# P05_CPLD.net
KiCad netlist of a schematic drawn in Altium Designer
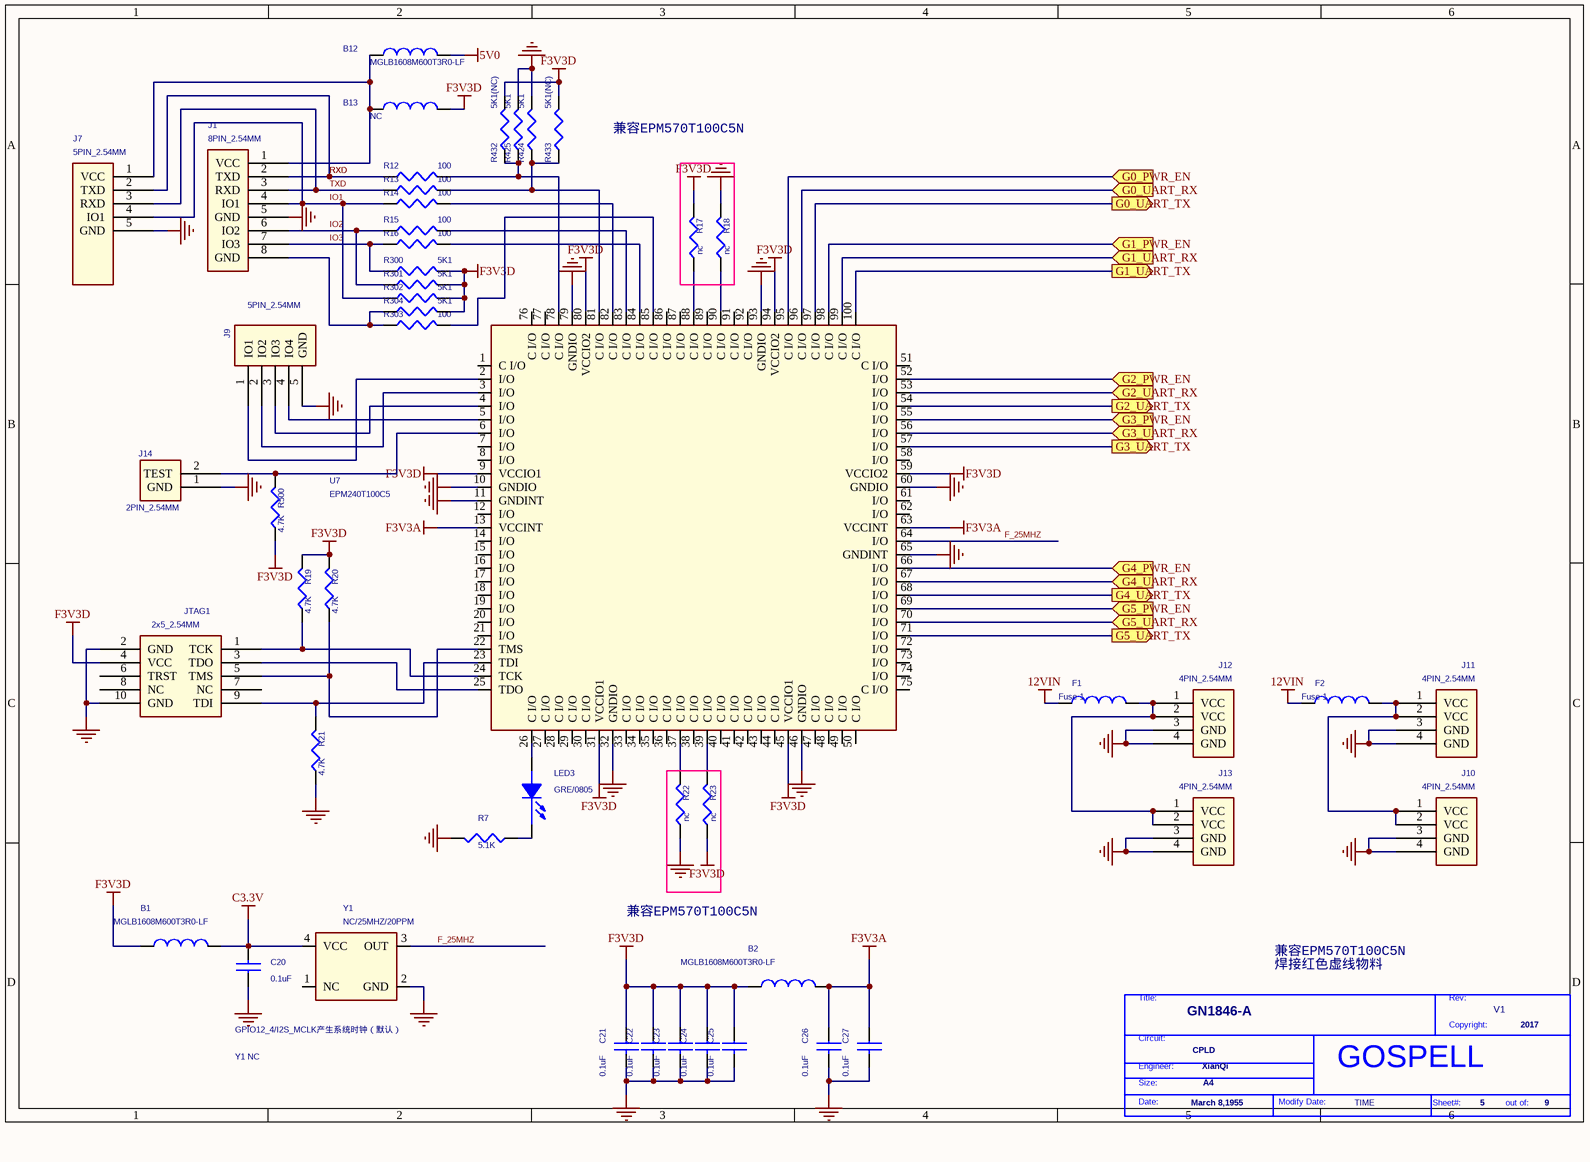
[diagram p0: P05 CPLD.SchDoc]

(export (version "E")
  (design (tool "Eeschema 10.0.6"))
  (components
    (comp (ref "B1") (value "MGLB1608M600T3R0-LF") (libsource (lib "*") (part "CHOKE TORROID_0")))
    (comp (ref "B2") (value "MGLB1608M600T3R0-LF") (libsource (lib "*") (part "CHOKE TORROID_0")))
    (comp (ref "B12") (value "MGLB1608M600T3R0-LF") (libsource (lib "*") (part "CHOKE TORROID_0")))
    (comp (ref "B13") (value "NC") (libsource (lib "*") (part "CHOKE TORROID_0")))
    (comp (ref "C20") (value "0.1uF") (libsource (lib "*") (part "CAP NP")))
    (comp (ref "C21") (value "0.1uF") (libsource (lib "*") (part "CAP NP_Dup1")))
    (comp (ref "C22") (value "0.1uF") (libsource (lib "*") (part "CAP NP_Dup1")))
    (comp (ref "C23") (value "0.1uF") (libsource (lib "*") (part "CAP NP_Dup1")))
    (comp (ref "C24") (value "0.1uF") (libsource (lib "*") (part "CAP NP_Dup1")))
    (comp (ref "C25") (value "0.1uF") (libsource (lib "*") (part "CAP NP_Dup1")))
    (comp (ref "C26") (value "0.1uF") (libsource (lib "*") (part "CAP NP_Dup1")))
    (comp (ref "C27") (value "0.1uF") (libsource (lib "*") (part "CAP NP_Dup1")))
    (comp (ref "F1") (value "Fuse 1") (libsource (lib "*") (part "CHOKE TORROID_0")))
    (comp (ref "F2") (value "Fuse 1") (libsource (lib "*") (part "CHOKE TORROID_0")))
    (comp (ref "J1") (value "8PIN_2.54MM") (libsource (lib "*") (part "CON8_0")))
    (comp (ref "J7") (value "5PIN_2.54MM") (libsource (lib "*") (part "CON8_1")))
    (comp (ref "J9") (value "5PIN_2.54MM") (libsource (lib "") (part "CON8_1_1")))
    (comp (ref "J10") (value "4PIN_2.54MM") (libsource (lib "GN-1846-A-V1") (part "CON8_1")))
    (comp (ref "J11") (value "4PIN_2.54MM") (libsource (lib "GN-1846-A-V1") (part "CON8_1")))
    (comp (ref "J12") (value "4PIN_2.54MM") (libsource (lib "GN-1846-A-V1") (part "CON8_1")))
    (comp (ref "J13") (value "4PIN_2.54MM") (libsource (lib "GN-1846-A-V1") (part "CON8_1")))
    (comp (ref "J14") (value "2PIN_2.54MM") (libsource (lib "GN-1846-A-V2") (part "CON8_1")))
    (comp (ref "JTAG1") (value "2x5_2.54MM") (libsource (lib "*") (part "CON10A_0")))
    (comp (ref "LED3") (value "GRE/0805") (libsource (lib "*") (part "LED_0")))
    (comp (ref "R7") (value "5.1K") (libsource (lib "") (part "R_Dup1_1")))
    (comp (ref "R12") (value "100") (libsource (lib "*") (part "R_Dup1")))
    (comp (ref "R13") (value "100") (libsource (lib "*") (part "R_Dup1")))
    (comp (ref "R14") (value "100") (libsource (lib "*") (part "R_Dup1")))
    (comp (ref "R15") (value "100") (libsource (lib "*") (part "R_Dup1")))
    (comp (ref "R16") (value "100") (libsource (lib "*") (part "R_Dup1")))
    (comp (ref "R17") (value "nc") (libsource (lib "*") (part "R_Dup1")))
    (comp (ref "R18") (value "nc") (libsource (lib "*") (part "R_Dup1")))
    (comp (ref "R19") (value "4.7K") (libsource (lib "*") (part "R_Dup1")))
    (comp (ref "R20") (value "4.7K") (libsource (lib "*") (part "R_Dup1")))
    (comp (ref "R21") (value "4.7K") (libsource (lib "*") (part "R_Dup1")))
    (comp (ref "R22") (value "nc") (libsource (lib "*") (part "R_Dup1")))
    (comp (ref "R23") (value "nc") (libsource (lib "*") (part "R_Dup1")))
    (comp (ref "R300") (value "5K1") (libsource (lib "*") (part "R_Dup1")))
    (comp (ref "R301") (value "5K1") (libsource (lib "*") (part "R_Dup1")))
    (comp (ref "R302") (value "5K1") (libsource (lib "*") (part "R_Dup1")))
    (comp (ref "R303") (value "100") (libsource (lib "*") (part "R_Dup1")))
    (comp (ref "R304") (value "5K1") (libsource (lib "*") (part "R_Dup1")))
    (comp (ref "R424") (value "5K1") (libsource (lib "") (part "R_Dup1_1")))
    (comp (ref "R425") (value "5K1") (libsource (lib "") (part "R_Dup1_1")))
    (comp (ref "R432") (value "5K1(NC)") (libsource (lib "") (part "R_Dup1_1")))
    (comp (ref "R433") (value "5K1(NC)") (libsource (lib "") (part "R_Dup1_1")))
    (comp (ref "R500") (value "4.7K") (libsource (lib "*") (part "R_Dup1")))
    (comp (ref "U7") (value "EPM240T100C5") (libsource (lib "*") (part "EPM240T100C5")))
    (comp (ref "Y1") (value "NC/25MHZ/20PPM") (footprint "SCXO_7.0X5.0") (libsource (lib "*") (part "SCXO")))
  )
  (nets
    (net (code "1") (name "/F_25MHZ") (class "Default")
      (node (ref "U7") (pin "64") (pinfunction "I/O_64") (pintype "passive"))
      (node (ref "Y1") (pin "3") (pinfunction "OUT_3") (pintype "passive"))
    )
    (net (code "2") (name "/G0_PWR_EN") (class "Default")
      (node (ref "U7") (pin "95") (pinfunction "C_I/O_95") (pintype "passive"))
    )
    (net (code "3") (name "/G0_UART_RX") (class "Default")
      (node (ref "U7") (pin "96") (pinfunction "C_I/O_96") (pintype "passive"))
    )
    (net (code "4") (name "/G0_UART_TX") (class "Default")
      (node (ref "U7") (pin "97") (pinfunction "C_I/O_97") (pintype "passive"))
    )
    (net (code "5") (name "/G1_PWR_EN") (class "Default")
      (node (ref "U7") (pin "98") (pinfunction "C_I/O_98") (pintype "passive"))
    )
    (net (code "6") (name "/G1_UART_RX") (class "Default")
      (node (ref "U7") (pin "99") (pinfunction "C_I/O_99") (pintype "passive"))
    )
    (net (code "7") (name "/G1_UART_TX") (class "Default")
      (node (ref "U7") (pin "100") (pinfunction "C_I/O_100") (pintype "passive"))
    )
    (net (code "8") (name "/G2_PWR_EN") (class "Default")
      (node (ref "U7") (pin "52") (pinfunction "I/O_52") (pintype "passive"))
    )
    (net (code "9") (name "/G2_UART_RX") (class "Default")
      (node (ref "U7") (pin "53") (pinfunction "I/O_53") (pintype "passive"))
    )
    (net (code "10") (name "/G2_UART_TX") (class "Default")
      (node (ref "U7") (pin "54") (pinfunction "I/O_54") (pintype "passive"))
    )
    (net (code "11") (name "/G3_PWR_EN") (class "Default")
      (node (ref "U7") (pin "55") (pinfunction "I/O_55") (pintype "passive"))
    )
    (net (code "12") (name "/G3_UART_RX") (class "Default")
      (node (ref "U7") (pin "56") (pinfunction "I/O_56") (pintype "passive"))
    )
    (net (code "13") (name "/G3_UART_TX") (class "Default")
      (node (ref "U7") (pin "57") (pinfunction "I/O_57") (pintype "passive"))
    )
    (net (code "14") (name "/G4_PWR_EN") (class "Default")
      (node (ref "U7") (pin "66") (pinfunction "I/O_66") (pintype "passive"))
    )
    (net (code "15") (name "/G4_UART_RX") (class "Default")
      (node (ref "U7") (pin "67") (pinfunction "I/O_67") (pintype "passive"))
    )
    (net (code "16") (name "/G4_UART_TX") (class "Default")
      (node (ref "U7") (pin "68") (pinfunction "I/O_68") (pintype "passive"))
    )
    (net (code "17") (name "/G5_PWR_EN") (class "Default")
      (node (ref "U7") (pin "69") (pinfunction "I/O_69") (pintype "passive"))
    )
    (net (code "18") (name "/G5_UART_RX") (class "Default")
      (node (ref "U7") (pin "70") (pinfunction "I/O_70") (pintype "passive"))
    )
    (net (code "19") (name "/G5_UART_TX") (class "Default")
      (node (ref "U7") (pin "71") (pinfunction "I/O_71") (pintype "passive"))
    )
    (net (code "20") (name "/IO1") (class "Default")
      (node (ref "J1") (pin "4") (pinfunction "IO1_4") (pintype "passive"))
      (node (ref "J7") (pin "4") (pinfunction "IO1_4") (pintype "passive"))
      (node (ref "R14") (pin "2") (pinfunction "2_2") (pintype "passive"))
      (node (ref "R302") (pin "2") (pinfunction "2_2") (pintype "passive"))
    )
    (net (code "21") (name "/IO2") (class "Default")
      (node (ref "J1") (pin "6") (pinfunction "IO2_6") (pintype "passive"))
      (node (ref "R15") (pin "2") (pinfunction "2_2") (pintype "passive"))
      (node (ref "R301") (pin "2") (pinfunction "2_2") (pintype "passive"))
    )
    (net (code "22") (name "/IO3") (class "Default")
      (node (ref "J1") (pin "7") (pinfunction "IO3_7") (pintype "passive"))
      (node (ref "R16") (pin "2") (pinfunction "2_2") (pintype "passive"))
      (node (ref "R300") (pin "2") (pinfunction "2_2") (pintype "passive"))
    )
    (net (code "23") (name "/RXD") (class "Default")
      (node (ref "J1") (pin "2") (pinfunction "TXD_2") (pintype "passive"))
      (node (ref "J7") (pin "2") (pinfunction "TXD_2") (pintype "passive"))
      (node (ref "R12") (pin "2") (pinfunction "2_2") (pintype "passive"))
    )
    (net (code "24") (name "/TXD") (class "Default")
      (node (ref "J1") (pin "3") (pinfunction "RXD_3") (pintype "passive"))
      (node (ref "J7") (pin "3") (pinfunction "RXD_3") (pintype "passive"))
      (node (ref "R13") (pin "2") (pinfunction "2_2") (pintype "passive"))
    )
    (net (code "25") (name "5V0") (class "Default")
      (node (ref "B12") (pin "2") (pinfunction "2_2") (pintype "passive"))
    )
    (net (code "26") (name "12VIN") (class "Default")
      (node (ref "F1") (pin "1") (pinfunction "1_1") (pintype "passive"))
      (node (ref "F2") (pin "1") (pinfunction "1_1") (pintype "passive"))
    )
    (net (code "27") (name "C3.3V") (class "Default")
      (node (ref "B1") (pin "2") (pinfunction "2_2") (pintype "passive"))
      (node (ref "C20") (pin "2") (pinfunction "2_2") (pintype "passive"))
      (node (ref "Y1") (pin "4") (pinfunction "VCC_4") (pintype "passive"))
    )
    (net (code "28") (name "F3V3A") (class "Default")
      (node (ref "B2") (pin "2") (pinfunction "2_2") (pintype "passive"))
      (node (ref "C26") (pin "1") (pinfunction "1_1") (pintype "passive"))
      (node (ref "C27") (pin "1") (pinfunction "1_1") (pintype "passive"))
      (node (ref "U7") (pin "13") (pinfunction "VCCINT_13") (pintype "passive"))
      (node (ref "U7") (pin "63") (pinfunction "VCCINT_63") (pintype "passive"))
    )
    (net (code "29") (name "F3V3D") (class "Default")
      (node (ref "B1") (pin "1") (pinfunction "1_1") (pintype "passive"))
      (node (ref "B13") (pin "2") (pinfunction "2_2") (pintype "passive"))
      (node (ref "B2") (pin "1") (pinfunction "1_1") (pintype "passive"))
      (node (ref "C21") (pin "1") (pinfunction "1_1") (pintype "passive"))
      (node (ref "C22") (pin "1") (pinfunction "1_1") (pintype "passive"))
      (node (ref "C23") (pin "1") (pinfunction "1_1") (pintype "passive"))
      (node (ref "C24") (pin "1") (pinfunction "1_1") (pintype "passive"))
      (node (ref "C25") (pin "1") (pinfunction "1_1") (pintype "passive"))
      (node (ref "JTAG1") (pin "4") (pinfunction "VCC_4") (pintype "passive"))
      (node (ref "R17") (pin "1") (pinfunction "1_1") (pintype "passive"))
      (node (ref "R19") (pin "1") (pinfunction "1_1") (pintype "passive"))
      (node (ref "R20") (pin "1") (pinfunction "1_1") (pintype "passive"))
      (node (ref "R23") (pin "2") (pinfunction "2_2") (pintype "passive"))
      (node (ref "R300") (pin "1") (pinfunction "1_1") (pintype "passive"))
      (node (ref "R301") (pin "1") (pinfunction "1_1") (pintype "passive"))
      (node (ref "R302") (pin "1") (pinfunction "1_1") (pintype "passive"))
      (node (ref "R304") (pin "1") (pinfunction "1_1") (pintype "passive"))
      (node (ref "R432") (pin "1") (pinfunction "1_1") (pintype "passive"))
      (node (ref "R433") (pin "1") (pinfunction "1_1") (pintype "passive"))
      (node (ref "R500") (pin "2") (pinfunction "2_2") (pintype "passive"))
      (node (ref "U7") (pin "31") (pinfunction "VCCIO1_31") (pintype "passive"))
      (node (ref "U7") (pin "45") (pinfunction "VCCIO1_45") (pintype "passive"))
      (node (ref "U7") (pin "59") (pinfunction "VCCIO2_59") (pintype "passive"))
      (node (ref "U7") (pin "80") (pinfunction "VCCIO2_80") (pintype "passive"))
      (node (ref "U7") (pin "9") (pinfunction "VCCIO1_9") (pintype "passive"))
      (node (ref "U7") (pin "94") (pinfunction "VCCIO2_94") (pintype "passive"))
    )
    (net (code "30") (name "GND") (class "Default")
      (node (ref "C20") (pin "1") (pinfunction "1_1") (pintype "passive"))
      (node (ref "C21") (pin "2") (pinfunction "2_2") (pintype "passive"))
      (node (ref "C22") (pin "2") (pinfunction "2_2") (pintype "passive"))
      (node (ref "C23") (pin "2") (pinfunction "2_2") (pintype "passive"))
      (node (ref "C24") (pin "2") (pinfunction "2_2") (pintype "passive"))
      (node (ref "C25") (pin "2") (pinfunction "2_2") (pintype "passive"))
      (node (ref "C26") (pin "2") (pinfunction "2_2") (pintype "passive"))
      (node (ref "C27") (pin "2") (pinfunction "2_2") (pintype "passive"))
      (node (ref "J1") (pin "5") (pinfunction "GND_5") (pintype "passive"))
      (node (ref "J10") (pin "3") (pinfunction "GND_3") (pintype "passive"))
      (node (ref "J10") (pin "4") (pinfunction "GND_4") (pintype "passive"))
      (node (ref "J11") (pin "3") (pinfunction "GND_3") (pintype "passive"))
      (node (ref "J11") (pin "4") (pinfunction "GND_4") (pintype "passive"))
      (node (ref "J12") (pin "3") (pinfunction "GND_3") (pintype "passive"))
      (node (ref "J12") (pin "4") (pinfunction "GND_4") (pintype "passive"))
      (node (ref "J13") (pin "3") (pinfunction "GND_3") (pintype "passive"))
      (node (ref "J13") (pin "4") (pinfunction "GND_4") (pintype "passive"))
      (node (ref "J14") (pin "1") (pinfunction "GND_1") (pintype "passive"))
      (node (ref "J7") (pin "5") (pinfunction "GND_5") (pintype "passive"))
      (node (ref "J9") (pin "5") (pinfunction "GND_5") (pintype "passive"))
      (node (ref "JTAG1") (pin "10") (pinfunction "GND_10") (pintype "passive"))
      (node (ref "JTAG1") (pin "2") (pinfunction "GND_2") (pintype "passive"))
      (node (ref "R18") (pin "1") (pinfunction "1_1") (pintype "passive"))
      (node (ref "R21") (pin "2") (pinfunction "2_2") (pintype "passive"))
      (node (ref "R22") (pin "2") (pinfunction "2_2") (pintype "passive"))
      (node (ref "R424") (pin "1") (pinfunction "1_1") (pintype "passive"))
      (node (ref "R425") (pin "1") (pinfunction "1_1") (pintype "passive"))
      (node (ref "R7") (pin "1") (pinfunction "1_1") (pintype "passive"))
      (node (ref "U7") (pin "10") (pinfunction "GNDIO_10") (pintype "passive"))
      (node (ref "U7") (pin "11") (pinfunction "GNDINT_11") (pintype "passive"))
      (node (ref "U7") (pin "32") (pinfunction "GNDIO_32") (pintype "passive"))
      (node (ref "U7") (pin "46") (pinfunction "GNDIO_46") (pintype "passive"))
      (node (ref "U7") (pin "60") (pinfunction "GNDIO_60") (pintype "passive"))
      (node (ref "U7") (pin "65") (pinfunction "GNDINT_65") (pintype "passive"))
      (node (ref "U7") (pin "79") (pinfunction "GNDIO_79") (pintype "passive"))
      (node (ref "U7") (pin "93") (pinfunction "GNDIO_93") (pintype "passive"))
      (node (ref "Y1") (pin "2") (pinfunction "GND_2") (pintype "passive"))
    )
    (net (code "31") (name "Net-(F1-Pad2)") (class "Default")
      (node (ref "F1") (pin "2") (pinfunction "2_2") (pintype "passive"))
      (node (ref "J12") (pin "1") (pinfunction "VCC_1") (pintype "passive"))
      (node (ref "J12") (pin "2") (pinfunction "VCC_2") (pintype "passive"))
      (node (ref "J13") (pin "1") (pinfunction "VCC_1") (pintype "passive"))
      (node (ref "J13") (pin "2") (pinfunction "VCC_2") (pintype "passive"))
    )
    (net (code "32") (name "Net-(F2-Pad2)") (class "Default")
      (node (ref "F2") (pin "2") (pinfunction "2_2") (pintype "passive"))
      (node (ref "J10") (pin "1") (pinfunction "VCC_1") (pintype "passive"))
      (node (ref "J10") (pin "2") (pinfunction "VCC_2") (pintype "passive"))
      (node (ref "J11") (pin "1") (pinfunction "VCC_1") (pintype "passive"))
      (node (ref "J11") (pin "2") (pinfunction "VCC_2") (pintype "passive"))
    )
    (net (code "33") (name "Net-(J1-GND-Pad8)") (class "Default")
      (node (ref "J1") (pin "8") (pinfunction "GND_8") (pintype "passive"))
      (node (ref "R303") (pin "2") (pinfunction "2_2") (pintype "passive"))
      (node (ref "R304") (pin "2") (pinfunction "2_2") (pintype "passive"))
    )
    (net (code "34") (name "Net-(J1-VCC)") (class "Default")
      (node (ref "B12") (pin "1") (pinfunction "1_1") (pintype "passive"))
      (node (ref "B13") (pin "1") (pinfunction "1_1") (pintype "passive"))
      (node (ref "J1") (pin "1") (pinfunction "VCC_1") (pintype "passive"))
      (node (ref "J7") (pin "1") (pinfunction "VCC_1") (pintype "passive"))
    )
    (net (code "35") (name "Net-(J9-IO1)") (class "Default")
      (node (ref "J9") (pin "1") (pinfunction "IO1_1") (pintype "passive"))
      (node (ref "U7") (pin "2") (pinfunction "I/O_2") (pintype "passive"))
    )
    (net (code "36") (name "Net-(J9-IO2)") (class "Default")
      (node (ref "J9") (pin "2") (pinfunction "IO2_2") (pintype "passive"))
      (node (ref "U7") (pin "3") (pinfunction "I/O_3") (pintype "passive"))
    )
    (net (code "37") (name "Net-(J9-IO3)") (class "Default")
      (node (ref "J9") (pin "3") (pinfunction "IO3_3") (pintype "passive"))
      (node (ref "U7") (pin "4") (pinfunction "I/O_4") (pintype "passive"))
    )
    (net (code "38") (name "Net-(J9-IO4)") (class "Default")
      (node (ref "J9") (pin "4") (pinfunction "IO4_4") (pintype "passive"))
      (node (ref "U7") (pin "5") (pinfunction "I/O_5") (pintype "passive"))
    )
    (net (code "39") (name "Net-(J14-TEST)") (class "Default")
      (node (ref "J14") (pin "2") (pinfunction "TEST_2") (pintype "passive"))
      (node (ref "R500") (pin "1") (pinfunction "1_1") (pintype "passive"))
      (node (ref "U7") (pin "6") (pinfunction "I/O_6") (pintype "passive"))
    )
    (net (code "40") (name "Net-(JTAG1-TCK)") (class "Default")
      (node (ref "JTAG1") (pin "1") (pinfunction "TCK_1") (pintype "passive"))
      (node (ref "R19") (pin "2") (pinfunction "2_2") (pintype "passive"))
      (node (ref "U7") (pin "24") (pinfunction "TCK_24") (pintype "passive"))
    )
    (net (code "41") (name "Net-(JTAG1-TDI)") (class "Default")
      (node (ref "JTAG1") (pin "9") (pinfunction "TDI_9") (pintype "passive"))
      (node (ref "R21") (pin "1") (pinfunction "1_1") (pintype "passive"))
      (node (ref "U7") (pin "23") (pinfunction "TDI_23") (pintype "passive"))
    )
    (net (code "42") (name "Net-(JTAG1-TDO)") (class "Default")
      (node (ref "JTAG1") (pin "3") (pinfunction "TDO_3") (pintype "passive"))
      (node (ref "U7") (pin "25") (pinfunction "TDO_25") (pintype "passive"))
    )
    (net (code "43") (name "Net-(JTAG1-TMS)") (class "Default")
      (node (ref "JTAG1") (pin "5") (pinfunction "TMS_5") (pintype "passive"))
      (node (ref "R20") (pin "2") (pinfunction "2_2") (pintype "passive"))
      (node (ref "U7") (pin "22") (pinfunction "TMS_22") (pintype "passive"))
    )
    (net (code "44") (name "Net-(LED3-ANODE)") (class "Default")
      (node (ref "LED3") (pin "A") (pinfunction "ANODE_A") (pintype "passive"))
      (node (ref "U7") (pin "26") (pinfunction "C_I/O_26") (pintype "passive"))
    )
    (net (code "45") (name "Net-(LED3-CATHODE)") (class "Default")
      (node (ref "LED3") (pin "K") (pinfunction "CATHODE_K") (pintype "passive"))
      (node (ref "R7") (pin "2") (pinfunction "2_2") (pintype "passive"))
    )
    (net (code "46") (name "Net-(R12-Pad1)") (class "Default")
      (node (ref "R12") (pin "1") (pinfunction "1_1") (pintype "passive"))
      (node (ref "R425") (pin "2") (pinfunction "2_2") (pintype "passive"))
      (node (ref "R432") (pin "2") (pinfunction "2_2") (pintype "passive"))
      (node (ref "U7") (pin "78") (pinfunction "C_I/O_78") (pintype "passive"))
    )
    (net (code "47") (name "Net-(R13-Pad1)") (class "Default")
      (node (ref "R13") (pin "1") (pinfunction "1_1") (pintype "passive"))
      (node (ref "R424") (pin "2") (pinfunction "2_2") (pintype "passive"))
      (node (ref "R433") (pin "2") (pinfunction "2_2") (pintype "passive"))
      (node (ref "U7") (pin "81") (pinfunction "C_I/O_81") (pintype "passive"))
    )
    (net (code "48") (name "Net-(R14-Pad1)") (class "Default")
      (node (ref "R14") (pin "1") (pinfunction "1_1") (pintype "passive"))
      (node (ref "U7") (pin "82") (pinfunction "C_I/O_82") (pintype "passive"))
    )
    (net (code "49") (name "Net-(R15-Pad1)") (class "Default")
      (node (ref "R15") (pin "1") (pinfunction "1_1") (pintype "passive"))
      (node (ref "U7") (pin "83") (pinfunction "C_I/O_83") (pintype "passive"))
    )
    (net (code "50") (name "Net-(R16-Pad1)") (class "Default")
      (node (ref "R16") (pin "1") (pinfunction "1_1") (pintype "passive"))
      (node (ref "U7") (pin "84") (pinfunction "C_I/O_84") (pintype "passive"))
    )
    (net (code "51") (name "Net-(R17-Pad2)") (class "Default")
      (node (ref "R17") (pin "2") (pinfunction "2_2") (pintype "passive"))
      (node (ref "U7") (pin "88") (pinfunction "C_I/O_88") (pintype "passive"))
    )
    (net (code "52") (name "Net-(R18-Pad2)") (class "Default")
      (node (ref "R18") (pin "2") (pinfunction "2_2") (pintype "passive"))
      (node (ref "U7") (pin "90") (pinfunction "C_I/O_90") (pintype "passive"))
    )
    (net (code "53") (name "Net-(R22-Pad1)") (class "Default")
      (node (ref "R22") (pin "1") (pinfunction "1_1") (pintype "passive"))
      (node (ref "U7") (pin "37") (pinfunction "C_I/O_37") (pintype "passive"))
    )
    (net (code "54") (name "Net-(R23-Pad1)") (class "Default")
      (node (ref "R23") (pin "1") (pinfunction "1_1") (pintype "passive"))
      (node (ref "U7") (pin "39") (pinfunction "C_I/O_39") (pintype "passive"))
    )
    (net (code "55") (name "Net-(R303-Pad1)") (class "Default")
      (node (ref "R303") (pin "1") (pinfunction "1_1") (pintype "passive"))
      (node (ref "U7") (pin "85") (pinfunction "C_I/O_85") (pintype "passive"))
    )
    (net (code "56") (name "unconnected-(JTAG1-NC-Pad7)") (class "Default")
      (node (ref "JTAG1") (pin "7") (pinfunction "NC_7") (pintype "passive"))
    )
    (net (code "57") (name "unconnected-(JTAG1-NC-Pad8)") (class "Default")
      (node (ref "JTAG1") (pin "8") (pinfunction "NC_8") (pintype "passive"))
    )
    (net (code "58") (name "unconnected-(JTAG1-TRST-Pad6)") (class "Default")
      (node (ref "JTAG1") (pin "6") (pinfunction "TRST_6") (pintype "passive"))
    )
    (net (code "59") (name "unconnected-(U7-C_I{slash}O-Pad1)") (class "Default")
      (node (ref "U7") (pin "1") (pinfunction "C_I/O_1") (pintype "passive"))
    )
    (net (code "60") (name "unconnected-(U7-C_I{slash}O-Pad27)") (class "Default")
      (node (ref "U7") (pin "27") (pinfunction "C_I/O_27") (pintype "passive"))
    )
    (net (code "61") (name "unconnected-(U7-C_I{slash}O-Pad28)") (class "Default")
      (node (ref "U7") (pin "28") (pinfunction "C_I/O_28") (pintype "passive"))
    )
    (net (code "62") (name "unconnected-(U7-C_I{slash}O-Pad29)") (class "Default")
      (node (ref "U7") (pin "29") (pinfunction "C_I/O_29") (pintype "passive"))
    )
    (net (code "63") (name "unconnected-(U7-C_I{slash}O-Pad30)") (class "Default")
      (node (ref "U7") (pin "30") (pinfunction "C_I/O_30") (pintype "passive"))
    )
    (net (code "64") (name "unconnected-(U7-C_I{slash}O-Pad33)") (class "Default")
      (node (ref "U7") (pin "33") (pinfunction "C_I/O_33") (pintype "passive"))
    )
    (net (code "65") (name "unconnected-(U7-C_I{slash}O-Pad34)") (class "Default")
      (node (ref "U7") (pin "34") (pinfunction "C_I/O_34") (pintype "passive"))
    )
    (net (code "66") (name "unconnected-(U7-C_I{slash}O-Pad35)") (class "Default")
      (node (ref "U7") (pin "35") (pinfunction "C_I/O_35") (pintype "passive"))
    )
    (net (code "67") (name "unconnected-(U7-C_I{slash}O-Pad36)") (class "Default")
      (node (ref "U7") (pin "36") (pinfunction "C_I/O_36") (pintype "passive"))
    )
    (net (code "68") (name "unconnected-(U7-C_I{slash}O-Pad38)") (class "Default")
      (node (ref "U7") (pin "38") (pinfunction "C_I/O_38") (pintype "passive"))
    )
    (net (code "69") (name "unconnected-(U7-C_I{slash}O-Pad40)") (class "Default")
      (node (ref "U7") (pin "40") (pinfunction "C_I/O_40") (pintype "passive"))
    )
    (net (code "70") (name "unconnected-(U7-C_I{slash}O-Pad41)") (class "Default")
      (node (ref "U7") (pin "41") (pinfunction "C_I/O_41") (pintype "passive"))
    )
    (net (code "71") (name "unconnected-(U7-C_I{slash}O-Pad42)") (class "Default")
      (node (ref "U7") (pin "42") (pinfunction "C_I/O_42") (pintype "passive"))
    )
    (net (code "72") (name "unconnected-(U7-C_I{slash}O-Pad43)") (class "Default")
      (node (ref "U7") (pin "43") (pinfunction "C_I/O_43") (pintype "passive"))
    )
    (net (code "73") (name "unconnected-(U7-C_I{slash}O-Pad44)") (class "Default")
      (node (ref "U7") (pin "44") (pinfunction "C_I/O_44") (pintype "passive"))
    )
    (net (code "74") (name "unconnected-(U7-C_I{slash}O-Pad47)") (class "Default")
      (node (ref "U7") (pin "47") (pinfunction "C_I/O_47") (pintype "passive"))
    )
    (net (code "75") (name "unconnected-(U7-C_I{slash}O-Pad48)") (class "Default")
      (node (ref "U7") (pin "48") (pinfunction "C_I/O_48") (pintype "passive"))
    )
    (net (code "76") (name "unconnected-(U7-C_I{slash}O-Pad49)") (class "Default")
      (node (ref "U7") (pin "49") (pinfunction "C_I/O_49") (pintype "passive"))
    )
    (net (code "77") (name "unconnected-(U7-C_I{slash}O-Pad50)") (class "Default")
      (node (ref "U7") (pin "50") (pinfunction "C_I/O_50") (pintype "passive"))
    )
    (net (code "78") (name "unconnected-(U7-C_I{slash}O-Pad51)") (class "Default")
      (node (ref "U7") (pin "51") (pinfunction "C_I/O_51") (pintype "passive"))
    )
    (net (code "79") (name "unconnected-(U7-C_I{slash}O-Pad75)") (class "Default")
      (node (ref "U7") (pin "75") (pinfunction "C_I/O_75") (pintype "passive"))
    )
    (net (code "80") (name "unconnected-(U7-C_I{slash}O-Pad76)") (class "Default")
      (node (ref "U7") (pin "76") (pinfunction "C_I/O_76") (pintype "passive"))
    )
    (net (code "81") (name "unconnected-(U7-C_I{slash}O-Pad77)") (class "Default")
      (node (ref "U7") (pin "77") (pinfunction "C_I/O_77") (pintype "passive"))
    )
    (net (code "82") (name "unconnected-(U7-C_I{slash}O-Pad86)") (class "Default")
      (node (ref "U7") (pin "86") (pinfunction "C_I/O_86") (pintype "passive"))
    )
    (net (code "83") (name "unconnected-(U7-C_I{slash}O-Pad87)") (class "Default")
      (node (ref "U7") (pin "87") (pinfunction "C_I/O_87") (pintype "passive"))
    )
    (net (code "84") (name "unconnected-(U7-C_I{slash}O-Pad89)") (class "Default")
      (node (ref "U7") (pin "89") (pinfunction "C_I/O_89") (pintype "passive"))
    )
    (net (code "85") (name "unconnected-(U7-C_I{slash}O-Pad91)") (class "Default")
      (node (ref "U7") (pin "91") (pinfunction "C_I/O_91") (pintype "passive"))
    )
    (net (code "86") (name "unconnected-(U7-C_I{slash}O-Pad92)") (class "Default")
      (node (ref "U7") (pin "92") (pinfunction "C_I/O_92") (pintype "passive"))
    )
    (net (code "87") (name "unconnected-(U7-I{slash}O-Pad7)") (class "Default")
      (node (ref "U7") (pin "7") (pinfunction "I/O_7") (pintype "passive"))
    )
    (net (code "88") (name "unconnected-(U7-I{slash}O-Pad8)") (class "Default")
      (node (ref "U7") (pin "8") (pinfunction "I/O_8") (pintype "passive"))
    )
    (net (code "89") (name "unconnected-(U7-I{slash}O-Pad12)") (class "Default")
      (node (ref "U7") (pin "12") (pinfunction "I/O_12") (pintype "passive"))
    )
    (net (code "90") (name "unconnected-(U7-I{slash}O-Pad14)") (class "Default")
      (node (ref "U7") (pin "14") (pinfunction "I/O_14") (pintype "passive"))
    )
    (net (code "91") (name "unconnected-(U7-I{slash}O-Pad15)") (class "Default")
      (node (ref "U7") (pin "15") (pinfunction "I/O_15") (pintype "passive"))
    )
    (net (code "92") (name "unconnected-(U7-I{slash}O-Pad16)") (class "Default")
      (node (ref "U7") (pin "16") (pinfunction "I/O_16") (pintype "passive"))
    )
    (net (code "93") (name "unconnected-(U7-I{slash}O-Pad17)") (class "Default")
      (node (ref "U7") (pin "17") (pinfunction "I/O_17") (pintype "passive"))
    )
    (net (code "94") (name "unconnected-(U7-I{slash}O-Pad18)") (class "Default")
      (node (ref "U7") (pin "18") (pinfunction "I/O_18") (pintype "passive"))
    )
    (net (code "95") (name "unconnected-(U7-I{slash}O-Pad19)") (class "Default")
      (node (ref "U7") (pin "19") (pinfunction "I/O_19") (pintype "passive"))
    )
    (net (code "96") (name "unconnected-(U7-I{slash}O-Pad20)") (class "Default")
      (node (ref "U7") (pin "20") (pinfunction "I/O_20") (pintype "passive"))
    )
    (net (code "97") (name "unconnected-(U7-I{slash}O-Pad21)") (class "Default")
      (node (ref "U7") (pin "21") (pinfunction "I/O_21") (pintype "passive"))
    )
    (net (code "98") (name "unconnected-(U7-I{slash}O-Pad58)") (class "Default")
      (node (ref "U7") (pin "58") (pinfunction "I/O_58") (pintype "passive"))
    )
    (net (code "99") (name "unconnected-(U7-I{slash}O-Pad61)") (class "Default")
      (node (ref "U7") (pin "61") (pinfunction "I/O_61") (pintype "passive"))
    )
    (net (code "100") (name "unconnected-(U7-I{slash}O-Pad62)") (class "Default")
      (node (ref "U7") (pin "62") (pinfunction "I/O_62") (pintype "passive"))
    )
    (net (code "101") (name "unconnected-(U7-I{slash}O-Pad72)") (class "Default")
      (node (ref "U7") (pin "72") (pinfunction "I/O_72") (pintype "passive"))
    )
    (net (code "102") (name "unconnected-(U7-I{slash}O-Pad73)") (class "Default")
      (node (ref "U7") (pin "73") (pinfunction "I/O_73") (pintype "passive"))
    )
    (net (code "103") (name "unconnected-(U7-I{slash}O-Pad74)") (class "Default")
      (node (ref "U7") (pin "74") (pinfunction "I/O_74") (pintype "passive"))
    )
    (net (code "104") (name "unconnected-(Y1-NC-Pad1)") (class "Default")
      (node (ref "Y1") (pin "1") (pinfunction "NC_1") (pintype "passive"))
    )
  )
)
